# untitled.net
KiCad netlist of a schematic drawn in EAGLE
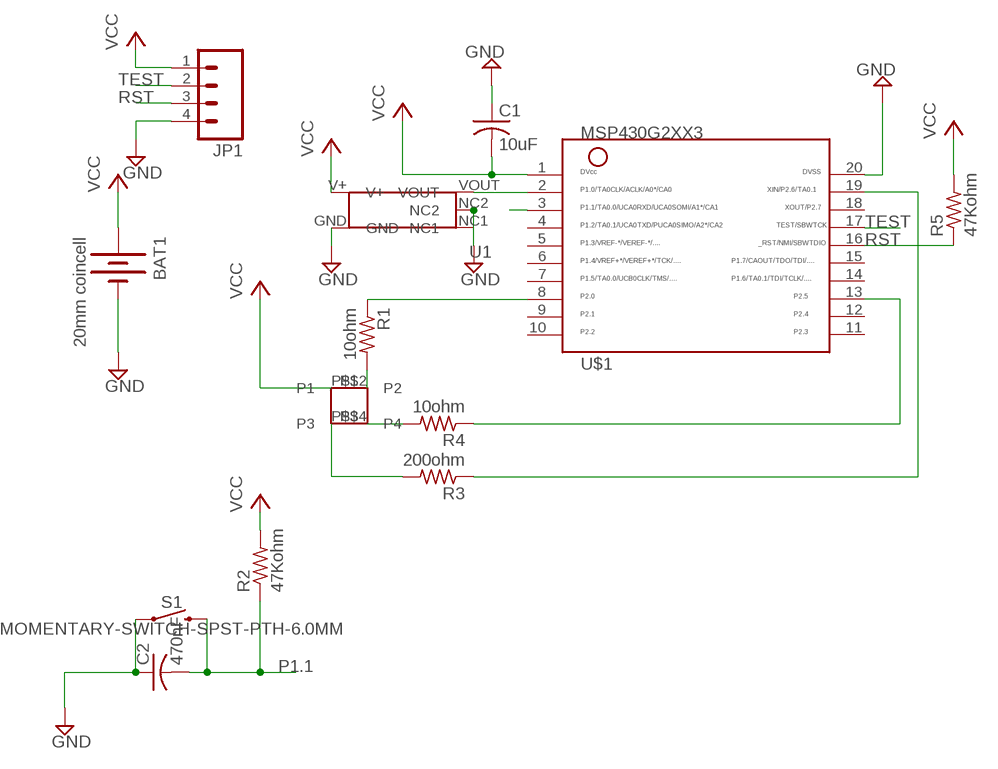
[diagram p0: schematic, sheet 1]

(export (version "E")
  (design (tool "Eeschema 10.0.6"))
  (components
    (comp (ref "BAT1")
      (value "20mm coincell")
      (footprint "eagle-import:BATTCON_20MM_PTH_COMPACT")
      (libsource (lib "eagle-import") (part "BATTERYFOB"))
    )
    (comp (ref "C1")
      (value "10uF")
      (footprint "eagle-import:C1206")
      (libsource (lib "eagle-import") (part "resistor_348_C-USC1206"))
    )
    (comp (ref "C2")
      (value "470nF")
      (footprint "eagle-import:C1206")
      (libsource (lib "eagle-import") (part "C-USC1206"))
    )
    (comp (ref "JP1")
      (value "M04LOCK")
      (footprint "eagle-import:1X04_LOCK")
      (libsource (lib "eagle-import") (part "M04LOCK"))
    )
    (comp (ref "R1")
      (value "10ohm")
      (footprint "eagle-import:R1206")
      (libsource (lib "eagle-import") (part "R-US_R1206"))
    )
    (comp (ref "R2")
      (value "47Kohm")
      (footprint "eagle-import:R1206")
      (libsource (lib "eagle-import") (part "R-US_R1206"))
    )
    (comp (ref "R3")
      (value "200ohm")
      (footprint "eagle-import:R1206")
      (libsource (lib "eagle-import") (part "R-US_R1206"))
    )
    (comp (ref "R4")
      (value "10ohm")
      (footprint "eagle-import:R1206")
      (libsource (lib "eagle-import") (part "R-US_R1206"))
    )
    (comp (ref "R5")
      (value "47Kohm")
      (footprint "eagle-import:R1206")
      (libsource (lib "eagle-import") (part "R-US_R1206"))
    )
    (comp (ref "S1")
      (value "MOMENTARY-SWITCH-SPST-PTH-6.0MM")
      (footprint "eagle-import:TACTILE_SWITCH_PTH_6.0MM")
      (libsource (lib "eagle-import") (part "MOMENTARY-SWITCH-SPST-PTH-6.0MM"))
    )
    (comp (ref "U$1")
      (value "MSP430G2XX3TSSOP")
      (footprint "eagle-import:PW20")
      (libsource (lib "eagle-import") (part "MSP430G2XX3TSSOP"))
    )
    (comp (ref "U$2")
      (value "RGB_LED")
      (footprint "eagle-import:1210RGB")
      (libsource (lib "eagle-import") (part "RGB_LED"))
    )
    (comp (ref "U1")
      (value "TEMPERATURE_SENSOR")
      (footprint "eagle-import:SOT_563")
      (libsource (lib "eagle-import") (part "TEMPERATURE_SENSOR"))
    )
  )
  (nets
    (net (code "1") (name "/P1.1") (class "Default")
      (node (ref "C2") (pin "2") (pinfunction "2_2") (pintype "passive"))
      (node (ref "R2") (pin "1") (pinfunction "1_1") (pintype "passive"))
      (node (ref "S1") (pin "3") (pinfunction "2_3") (pintype "passive"))
      (node (ref "U$1") (pin "3") (pinfunction "3_3") (pintype "bidirectional"))
    )
    (net (code "2") (name "/RST") (class "Default")
      (node (ref "JP1") (pin "3") (pinfunction "3_3") (pintype "passive"))
      (node (ref "R5") (pin "1") (pinfunction "1_1") (pintype "passive"))
      (node (ref "U$1") (pin "16") (pinfunction "16_16") (pintype "bidirectional"))
    )
    (net (code "3") (name "/TEST") (class "Default")
      (node (ref "JP1") (pin "2") (pinfunction "2_2") (pintype "passive"))
      (node (ref "U$1") (pin "17") (pinfunction "17_17") (pintype "bidirectional"))
    )
    (net (code "4") (name "GND") (class "Default")
      (node (ref "BAT1") (pin "2") (pinfunction "-_2") (pintype "power_in"))
      (node (ref "C1") (pin "1") (pinfunction "1_1") (pintype "passive"))
      (node (ref "C2") (pin "1") (pinfunction "1_1") (pintype "passive"))
      (node (ref "JP1") (pin "4") (pinfunction "4_4") (pintype "passive"))
      (node (ref "S1") (pin "1") (pinfunction "1_1") (pintype "passive"))
      (node (ref "U$1") (pin "20") (pinfunction "20_20") (pintype "bidirectional"))
      (node (ref "U1") (pin "GND") (pinfunction "GND_GND") (pintype "bidirectional"))
      (node (ref "U1") (pin "NC1") (pinfunction "NC1_NC1") (pintype "bidirectional"))
      (node (ref "U1") (pin "NC2") (pinfunction "NC2_NC2") (pintype "bidirectional"))
    )
    (net (code "5") (name "Net-(R1-Pad1)") (class "Default")
      (node (ref "R1") (pin "1") (pinfunction "1_1") (pintype "passive"))
      (node (ref "U$1") (pin "8") (pinfunction "8_8") (pintype "bidirectional"))
    )
    (net (code "6") (name "Net-(R3-Pad1)") (class "Default")
      (node (ref "R3") (pin "1") (pinfunction "1_1") (pintype "passive"))
      (node (ref "U$1") (pin "19") (pinfunction "19_19") (pintype "bidirectional"))
    )
    (net (code "7") (name "Net-(R4-Pad1)") (class "Default")
      (node (ref "R4") (pin "1") (pinfunction "1_1") (pintype "passive"))
      (node (ref "U$1") (pin "13") (pinfunction "13_13") (pintype "bidirectional"))
    )
    (net (code "8") (name "Net-(U$1-Pad2)") (class "Default")
      (node (ref "U$1") (pin "2") (pinfunction "2_2") (pintype "bidirectional"))
      (node (ref "U1") (pin "VOUT") (pinfunction "VOUT_VOUT") (pintype "bidirectional"))
    )
    (net (code "9") (name "Net-(U$2-P2)") (class "Default")
      (node (ref "R1") (pin "2") (pinfunction "2_2") (pintype "passive"))
      (node (ref "U$2") (pin "P$2") (pinfunction "P2_P$2") (pintype "bidirectional"))
    )
    (net (code "10") (name "Net-(U$2-P3)") (class "Default")
      (node (ref "R3") (pin "2") (pinfunction "2_2") (pintype "passive"))
      (node (ref "U$2") (pin "P$3") (pinfunction "P3_P$3") (pintype "bidirectional"))
    )
    (net (code "11") (name "Net-(U$2-P4)") (class "Default")
      (node (ref "R4") (pin "2") (pinfunction "2_2") (pintype "passive"))
      (node (ref "U$2") (pin "P$4") (pinfunction "P4_P$4") (pintype "bidirectional"))
    )
    (net (code "12") (name "VCC") (class "Default")
      (node (ref "BAT1") (pin "1") (pinfunction "+_1") (pintype "power_in"))
      (node (ref "BAT1") (pin "3") (pinfunction "+_3") (pintype "power_in"))
      (node (ref "BAT1") (pin "4") (pinfunction "+_4") (pintype "power_in"))
      (node (ref "BAT1") (pin "5") (pinfunction "+_5") (pintype "power_in"))
      (node (ref "C1") (pin "2") (pinfunction "2_2") (pintype "passive"))
      (node (ref "JP1") (pin "1") (pinfunction "1_1") (pintype "passive"))
      (node (ref "R2") (pin "2") (pinfunction "2_2") (pintype "passive"))
      (node (ref "R5") (pin "2") (pinfunction "2_2") (pintype "passive"))
      (node (ref "U$1") (pin "1") (pinfunction "1_1") (pintype "bidirectional"))
      (node (ref "U$2") (pin "P$1") (pinfunction "P1_P$1") (pintype "bidirectional"))
      (node (ref "U1") (pin "V+") (pinfunction "V+_V+") (pintype "bidirectional"))
    )
    (net (code "13") (name "unconnected-(U$1-Pad4)") (class "Default")
      (node (ref "U$1") (pin "4") (pinfunction "4_4") (pintype "bidirectional"))
    )
    (net (code "14") (name "unconnected-(U$1-Pad5)") (class "Default")
      (node (ref "U$1") (pin "5") (pinfunction "5_5") (pintype "bidirectional"))
    )
    (net (code "15") (name "unconnected-(U$1-Pad6)") (class "Default")
      (node (ref "U$1") (pin "6") (pinfunction "6_6") (pintype "bidirectional"))
    )
    (net (code "16") (name "unconnected-(U$1-Pad7)") (class "Default")
      (node (ref "U$1") (pin "7") (pinfunction "7_7") (pintype "bidirectional"))
    )
    (net (code "17") (name "unconnected-(U$1-Pad9)") (class "Default")
      (node (ref "U$1") (pin "9") (pinfunction "9_9") (pintype "bidirectional"))
    )
    (net (code "18") (name "unconnected-(U$1-Pad10)") (class "Default")
      (node (ref "U$1") (pin "10") (pinfunction "10_10") (pintype "bidirectional"))
    )
    (net (code "19") (name "unconnected-(U$1-Pad11)") (class "Default")
      (node (ref "U$1") (pin "11") (pinfunction "11_11") (pintype "bidirectional"))
    )
    (net (code "20") (name "unconnected-(U$1-Pad12)") (class "Default")
      (node (ref "U$1") (pin "12") (pinfunction "12_12") (pintype "bidirectional"))
    )
    (net (code "21") (name "unconnected-(U$1-Pad14)") (class "Default")
      (node (ref "U$1") (pin "14") (pinfunction "14_14") (pintype "bidirectional"))
    )
    (net (code "22") (name "unconnected-(U$1-Pad15)") (class "Default")
      (node (ref "U$1") (pin "15") (pinfunction "15_15") (pintype "bidirectional"))
    )
    (net (code "23") (name "unconnected-(U$1-Pad18)") (class "Default")
      (node (ref "U$1") (pin "18") (pinfunction "18_18") (pintype "bidirectional"))
    )
  )
)
